# 02-PowerSupply.net
KiCad netlist of a schematic drawn in Altium Designer
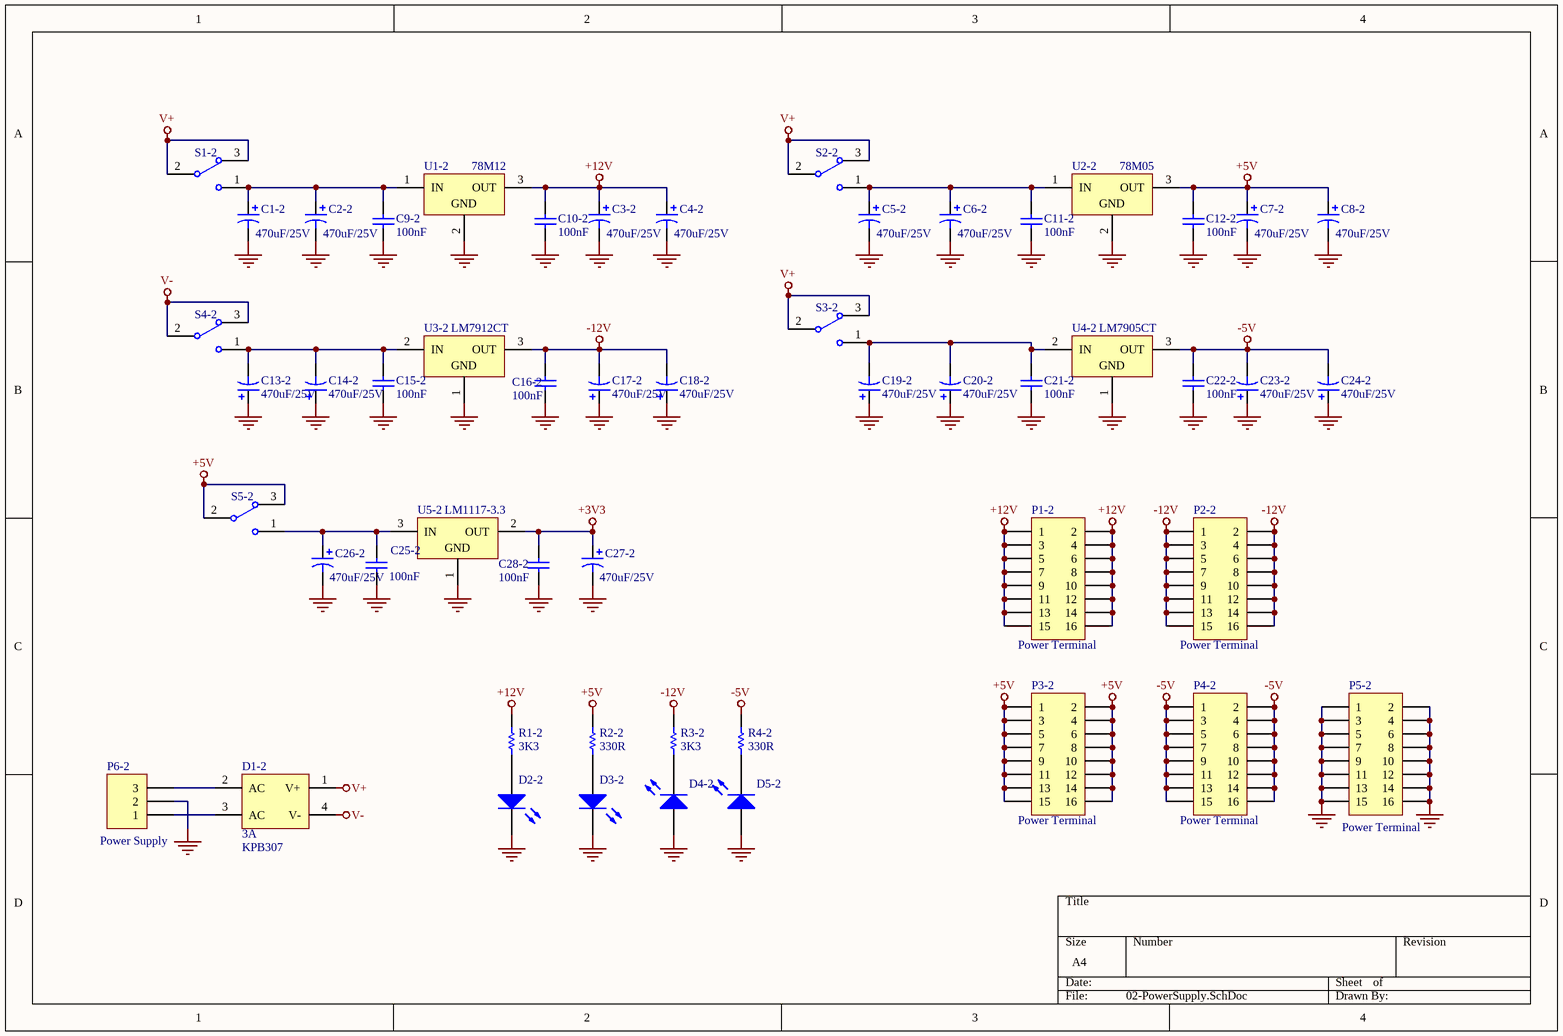
[diagram p0: 02-PowerSupply.SchDoc]

(export (version "E")
  (design (tool "Eeschema 10.0.6"))
  (components
    (comp (ref "C1-2")
      (value "470uF/25V")
      (footprint "C-ALU-10x10mm")
      (description "Polarized Capacitor (Radial)")
      (libsource (lib "Miscellaneous Devices") (part "Cap Pol1"))
    )
    (comp (ref "C2-2")
      (value "470uF/25V")
      (footprint "C-ALU-10x10mm")
      (description "Polarized Capacitor (Radial)")
      (libsource (lib "Miscellaneous Devices") (part "Cap Pol1"))
    )
    (comp (ref "C3-2")
      (value "470uF/25V")
      (footprint "C-ALU-10x10mm")
      (description "Polarized Capacitor (Radial)")
      (libsource (lib "Miscellaneous Devices") (part "Cap Pol1"))
    )
    (comp (ref "C4-2")
      (value "470uF/25V")
      (footprint "C-ALU-10x10mm")
      (description "Polarized Capacitor (Radial)")
      (libsource (lib "Miscellaneous Devices") (part "Cap Pol1"))
    )
    (comp (ref "C5-2")
      (value "470uF/25V")
      (footprint "C-ALU-10x10mm")
      (description "Polarized Capacitor (Radial)")
      (libsource (lib "Miscellaneous Devices") (part "Cap Pol1"))
    )
    (comp (ref "C6-2")
      (value "470uF/25V")
      (footprint "C-ALU-10x10mm")
      (description "Polarized Capacitor (Radial)")
      (libsource (lib "Miscellaneous Devices") (part "Cap Pol1"))
    )
    (comp (ref "C7-2")
      (value "470uF/25V")
      (footprint "C-ALU-10x10mm")
      (description "Polarized Capacitor (Radial)")
      (libsource (lib "Miscellaneous Devices") (part "Cap Pol1"))
    )
    (comp (ref "C8-2")
      (value "470uF/25V")
      (footprint "C-ALU-10x10mm")
      (description "Polarized Capacitor (Radial)")
      (libsource (lib "Miscellaneous Devices") (part "Cap Pol1"))
    )
    (comp (ref "C9-2")
      (value "100nF")
      (footprint "c-0805")
      (description "Capacitor")
      (fields
        (field (name "MANUFACTURER") "Generic Components")
        (field (name "Comment") "104")
        (field (name "PUBLISHER") "Altium Hobart Technology Centre")
      )
      (libsource (lib "Miscellaneous Devices") (part "Cap"))
    )
    (comp (ref "C10-2")
      (value "100nF")
      (footprint "c-0805")
      (description "Capacitor")
      (fields
        (field (name "MANUFACTURER") "Generic Components")
        (field (name "Comment") "104")
        (field (name "PUBLISHER") "Altium Hobart Technology Centre")
      )
      (libsource (lib "Miscellaneous Devices") (part "Cap"))
    )
    (comp (ref "C11-2")
      (value "100nF")
      (footprint "c-0805")
      (description "Capacitor")
      (fields
        (field (name "MANUFACTURER") "Generic Components")
        (field (name "Comment") "104")
        (field (name "PUBLISHER") "Altium Hobart Technology Centre")
      )
      (libsource (lib "Miscellaneous Devices") (part "Cap"))
    )
    (comp (ref "C12-2")
      (value "100nF")
      (footprint "c-0805")
      (description "Capacitor")
      (fields
        (field (name "MANUFACTURER") "Generic Components")
        (field (name "Comment") "104")
        (field (name "PUBLISHER") "Altium Hobart Technology Centre")
      )
      (libsource (lib "Miscellaneous Devices") (part "Cap"))
    )
    (comp (ref "C13-2")
      (value "470uF/25V")
      (footprint "C-ALU-10x10mm")
      (description "Polarized Capacitor (Radial)")
      (libsource (lib "Miscellaneous Devices") (part "Cap Pol1"))
    )
    (comp (ref "C14-2")
      (value "470uF/25V")
      (footprint "C-ALU-10x10mm")
      (description "Polarized Capacitor (Radial)")
      (libsource (lib "Miscellaneous Devices") (part "Cap Pol1"))
    )
    (comp (ref "C15-2")
      (value "100nF")
      (footprint "c-0805")
      (description "Capacitor")
      (fields
        (field (name "MANUFACTURER") "Generic Components")
        (field (name "Comment") "104")
        (field (name "PUBLISHER") "Altium Hobart Technology Centre")
      )
      (libsource (lib "Miscellaneous Devices") (part "Cap"))
    )
    (comp (ref "C16-2")
      (value "100nF")
      (footprint "c-0805")
      (description "Capacitor")
      (fields
        (field (name "MANUFACTURER") "Generic Components")
        (field (name "Comment") "104")
        (field (name "PUBLISHER") "Altium Hobart Technology Centre")
      )
      (libsource (lib "Miscellaneous Devices") (part "Cap"))
    )
    (comp (ref "C17-2")
      (value "470uF/25V")
      (footprint "C-ALU-10x10mm")
      (description "Polarized Capacitor (Radial)")
      (libsource (lib "Miscellaneous Devices") (part "Cap Pol1"))
    )
    (comp (ref "C18-2")
      (value "470uF/25V")
      (footprint "C-ALU-10x10mm")
      (description "Polarized Capacitor (Radial)")
      (libsource (lib "Miscellaneous Devices") (part "Cap Pol1"))
    )
    (comp (ref "C19-2")
      (value "470uF/25V")
      (footprint "C-ALU-10x10mm")
      (description "Polarized Capacitor (Radial)")
      (libsource (lib "Miscellaneous Devices") (part "Cap Pol1"))
    )
    (comp (ref "C20-2")
      (value "470uF/25V")
      (footprint "C-ALU-10x10mm")
      (description "Polarized Capacitor (Radial)")
      (libsource (lib "Miscellaneous Devices") (part "Cap Pol1"))
    )
    (comp (ref "C21-2")
      (value "100nF")
      (footprint "c-0805")
      (description "Capacitor")
      (fields
        (field (name "MANUFACTURER") "Generic Components")
        (field (name "Comment") "104")
        (field (name "PUBLISHER") "Altium Hobart Technology Centre")
      )
      (libsource (lib "Miscellaneous Devices") (part "Cap"))
    )
    (comp (ref "C22-2")
      (value "100nF")
      (footprint "c-0805")
      (description "Capacitor")
      (fields
        (field (name "MANUFACTURER") "Generic Components")
        (field (name "Comment") "104")
        (field (name "PUBLISHER") "Altium Hobart Technology Centre")
      )
      (libsource (lib "Miscellaneous Devices") (part "Cap"))
    )
    (comp (ref "C23-2")
      (value "470uF/25V")
      (footprint "C-ALU-10x10mm")
      (description "Polarized Capacitor (Radial)")
      (libsource (lib "Miscellaneous Devices") (part "Cap Pol1"))
    )
    (comp (ref "C24-2")
      (value "470uF/25V")
      (footprint "C-ALU-10x10mm")
      (description "Polarized Capacitor (Radial)")
      (libsource (lib "Miscellaneous Devices") (part "Cap Pol1"))
    )
    (comp (ref "C25-2")
      (value "100nF")
      (footprint "c-0805")
      (description "Capacitor")
      (fields
        (field (name "MANUFACTURER") "Generic Components")
        (field (name "Comment") "104")
        (field (name "PUBLISHER") "Altium Hobart Technology Centre")
      )
      (libsource (lib "Miscellaneous Devices") (part "Cap"))
    )
    (comp (ref "C26-2")
      (value "470uF/25V")
      (footprint "C-ALU-10x10mm")
      (description "Polarized Capacitor (Radial)")
      (libsource (lib "Miscellaneous Devices") (part "Cap Pol1"))
    )
    (comp (ref "C27-2")
      (value "470uF/25V")
      (footprint "C-ALU-10x10mm")
      (description "Polarized Capacitor (Radial)")
      (libsource (lib "Miscellaneous Devices") (part "Cap Pol1"))
    )
    (comp (ref "C28-2")
      (value "100nF")
      (footprint "c-0805")
      (description "Capacitor")
      (fields
        (field (name "MANUFACTURER") "Generic Components")
        (field (name "Comment") "104")
        (field (name "PUBLISHER") "Altium Hobart Technology Centre")
      )
      (libsource (lib "Miscellaneous Devices") (part "Cap"))
    )
    (comp (ref "D1-2")
      (value "KPB307")
      (footprint "D-DB-3A")
      (description "Diode Bridge")
      (fields (field (name "ALTIUM_VALUE") "3A"))
      (libsource (lib "Miscellaneous Devices") (part "Bridge2"))
    )
    (comp (ref "D2-2")
      (value "LED")
      (footprint "LED-0805")
      (description "Typical INFRARED GaAs LED")
      (fields (field (name "PUBLISHER") "Altium Limited"))
      (libsource (lib "Miscellaneous Devices") (part "LED0"))
    )
    (comp (ref "D3-2")
      (value "LED")
      (footprint "LED-0805")
      (description "Typical INFRARED GaAs LED")
      (fields (field (name "PUBLISHER") "Altium Limited"))
      (libsource (lib "Miscellaneous Devices") (part "LED0"))
    )
    (comp (ref "D4-2")
      (value "LED")
      (footprint "LED-0805")
      (description "Typical INFRARED GaAs LED")
      (fields (field (name "PUBLISHER") "Altium Limited"))
      (libsource (lib "Miscellaneous Devices") (part "LED0"))
    )
    (comp (ref "D5-2")
      (value "LED")
      (footprint "LED-0805")
      (description "Typical INFRARED GaAs LED")
      (fields (field (name "PUBLISHER") "Altium Limited"))
      (libsource (lib "Miscellaneous Devices") (part "LED0"))
    )
    (comp (ref "P1-2")
      (value "Power Terminal")
      (footprint "JP2.54-F-2x08A")
      (description "Header, 8-Pin, Dual row")
      (fields (field (name "Comment") "Header 8X2"))
      (libsource (lib "Miscellaneous Connectors") (part "Header 8X2"))
    )
    (comp (ref "P2-2")
      (value "Power Terminal")
      (footprint "JP2.54-F-2x08A")
      (description "Header, 8-Pin, Dual row")
      (fields (field (name "Comment") "Header 8X2"))
      (libsource (lib "Miscellaneous Connectors") (part "Header 8X2"))
    )
    (comp (ref "P3-2")
      (value "Power Terminal")
      (footprint "JP2.54-F-2x08A")
      (description "Header, 8-Pin, Dual row")
      (fields (field (name "Comment") "Header 8X2"))
      (libsource (lib "Miscellaneous Connectors") (part "Header 8X2"))
    )
    (comp (ref "P4-2")
      (value "Power Terminal")
      (footprint "JP2.54-F-2x08A")
      (description "Header, 8-Pin, Dual row")
      (fields (field (name "Comment") "Header 8X2"))
      (libsource (lib "Miscellaneous Connectors") (part "Header 8X2"))
    )
    (comp (ref "P5-2")
      (value "Power Terminal")
      (footprint "JP2.54-F-2x08A")
      (description "Header, 8-Pin, Dual row")
      (fields (field (name "Comment") "Header 8X2"))
      (libsource (lib "Miscellaneous Connectors") (part "Header 8X2"))
    )
    (comp (ref "P6-2")
      (value "Power Supply")
      (footprint "TER-KF128-3")
      (description "Header, 3-Pin")
      (fields (field (name "Comment") "H3"))
      (libsource (lib "Miscellaneous Connectors") (part "Header 3"))
    )
    (comp (ref "R1-2")
      (value "3K3")
      (footprint "R-0805")
      (description "Resistor")
      (fields (field (name "Comment") "332") (field (name "PUBLISHER") "Altium Limited"))
      (libsource (lib "Miscellaneous Devices") (part "Res1"))
    )
    (comp (ref "R2-2")
      (value "330R")
      (footprint "R-0805")
      (description "Resistor")
      (fields (field (name "Comment") "331") (field (name "PUBLISHER") "Altium Limited"))
      (libsource (lib "Miscellaneous Devices") (part "Res1"))
    )
    (comp (ref "R3-2")
      (value "3K3")
      (footprint "R-0805")
      (description "Resistor")
      (fields (field (name "Comment") "332") (field (name "PUBLISHER") "Altium Limited"))
      (libsource (lib "Miscellaneous Devices") (part "Res1"))
    )
    (comp (ref "R4-2")
      (value "330R")
      (footprint "R-0805")
      (description "Resistor")
      (fields (field (name "Comment") "331") (field (name "PUBLISHER") "Altium Limited"))
      (libsource (lib "Miscellaneous Devices") (part "Res1"))
    )
    (comp (ref "S1-2")
      (value "SW-SPDT")
      (footprint "SW-SLIDE-2P-2W")
      (description "SPDT Subminiature Toggle Switch, Right Angle Mounting, Vertical Actuation")
      (libsource (lib "Miscellaneous Devices") (part "SW-SPDT"))
    )
    (comp (ref "S2-2")
      (value "SW-SPDT")
      (footprint "SW-SLIDE-2P-2W")
      (description "SPDT Subminiature Toggle Switch, Right Angle Mounting, Vertical Actuation")
      (libsource (lib "Miscellaneous Devices") (part "SW-SPDT"))
    )
    (comp (ref "S3-2")
      (value "SW-SPDT")
      (footprint "SW-SLIDE-2P-2W")
      (description "SPDT Subminiature Toggle Switch, Right Angle Mounting, Vertical Actuation")
      (libsource (lib "Miscellaneous Devices") (part "SW-SPDT"))
    )
    (comp (ref "S4-2")
      (value "SW-SPDT")
      (footprint "SW-SLIDE-2P-2W")
      (description "SPDT Subminiature Toggle Switch, Right Angle Mounting, Vertical Actuation")
      (libsource (lib "Miscellaneous Devices") (part "SW-SPDT"))
    )
    (comp (ref "S5-2")
      (value "SW-SPDT")
      (footprint "SW-SLIDE-2P-2W")
      (description "SPDT Subminiature Toggle Switch, Right Angle Mounting, Vertical Actuation")
      (libsource (lib "Miscellaneous Devices") (part "SW-SPDT"))
    )
    (comp (ref "U1-2")
      (value "78M12")
      (footprint "TO-252-3")
      (description "3-Terminal Positive Voltage Regulators, 3-pin TO-220")
      (fields
        (field (name "PARTNUMBER") "LM78M05CT")
        (field (name "MANUFACTURER") "National Semiconductor")
        (field (name "PUBLISHER") "Altium Limited")
      )
      (libsource (lib "NSC LDO") (part "LM78M05CT"))
    )
    (comp (ref "U2-2")
      (value "78M05")
      (footprint "TO-252-3")
      (description "3-Terminal Positive Voltage Regulators, 3-pin TO-220")
      (fields
        (field (name "PARTNUMBER") "LM78M05CT")
        (field (name "MANUFACTURER") "National Semiconductor")
        (field (name "PUBLISHER") "Altium Limited")
      )
      (libsource (lib "NSC LDO") (part "LM78M05CT"))
    )
    (comp (ref "U3-2")
      (value "LM7912CT")
      (footprint "TO-263-3")
      (description "3-Terminal Negative Regulators, 3-pin TO-220")
      (fields
        (field (name "PARTNUMBER") "LM79M12CT")
        (field (name "MANUFACTURER") "National Semiconductor")
        (field (name "PUBLISHER") "Altium Limited")
      )
      (libsource (lib "NSC LDO") (part "LM79M12CT"))
    )
    (comp (ref "U4-2")
      (value "LM7905CT")
      (footprint "TO-263-3")
      (description "3-Terminal Negative Regulators, 3-pin TO-220")
      (fields
        (field (name "PARTNUMBER") "LM79M12CT")
        (field (name "MANUFACTURER") "National Semiconductor")
        (field (name "PUBLISHER") "Altium Limited")
      )
      (libsource (lib "NSC LDO") (part "LM79M12CT"))
    )
    (comp (ref "U5-2")
      (value "LM1117-3.3")
      (footprint "SOT-223-3")
      (description "800mA Low-Dropout Linear Regulator, 3-pin TO-252")
      (fields
        (field (name "PARTNUMBER") "LM1117IDTX-3.3")
        (field (name "MANUFACTURER") "National Semiconductor")
        (field (name "PUBLISHER") "Altium Limited")
      )
      (libsource (lib "NSC LDO") (part "LM1117IDTX-3.3"))
    )
  )
  (nets
    (net (code "1") (name "+3V3") (class "Default")
      (node (ref "C27-2") (pin "1") (pinfunction "1_1") (pintype "passive"))
      (node (ref "C28-2") (pin "2") (pinfunction "2_2") (pintype "passive"))
      (node (ref "U5-2") (pin "2") (pinfunction "OUT_2") (pintype "power_in"))
    )
    (net (code "2") (name "+5V") (class "Default")
      (node (ref "C12-2") (pin "2") (pinfunction "2_2") (pintype "passive"))
      (node (ref "C7-2") (pin "1") (pinfunction "1_1") (pintype "passive"))
      (node (ref "C8-2") (pin "1") (pinfunction "1_1") (pintype "passive"))
      (node (ref "P3-2") (pin "1") (pinfunction "1_1") (pintype "passive"))
      (node (ref "P3-2") (pin "10") (pinfunction "10_10") (pintype "passive"))
      (node (ref "P3-2") (pin "11") (pinfunction "11_11") (pintype "passive"))
      (node (ref "P3-2") (pin "12") (pinfunction "12_12") (pintype "passive"))
      (node (ref "P3-2") (pin "13") (pinfunction "13_13") (pintype "passive"))
      (node (ref "P3-2") (pin "14") (pinfunction "14_14") (pintype "passive"))
      (node (ref "P3-2") (pin "15") (pinfunction "15_15") (pintype "passive"))
      (node (ref "P3-2") (pin "16") (pinfunction "16_16") (pintype "passive"))
      (node (ref "P3-2") (pin "2") (pinfunction "2_2") (pintype "passive"))
      (node (ref "P3-2") (pin "3") (pinfunction "3_3") (pintype "passive"))
      (node (ref "P3-2") (pin "4") (pinfunction "4_4") (pintype "passive"))
      (node (ref "P3-2") (pin "5") (pinfunction "5_5") (pintype "passive"))
      (node (ref "P3-2") (pin "6") (pinfunction "6_6") (pintype "passive"))
      (node (ref "P3-2") (pin "7") (pinfunction "7_7") (pintype "passive"))
      (node (ref "P3-2") (pin "8") (pinfunction "8_8") (pintype "passive"))
      (node (ref "P3-2") (pin "9") (pinfunction "9_9") (pintype "passive"))
      (node (ref "R2-2") (pin "1") (pinfunction "1_1") (pintype "passive"))
      (node (ref "S5-2") (pin "2") (pinfunction "2_2") (pintype "passive"))
      (node (ref "S5-2") (pin "3") (pinfunction "3_3") (pintype "passive"))
      (node (ref "U2-2") (pin "3") (pinfunction "OUT_3") (pintype "power_in"))
    )
    (net (code "3") (name "+12V") (class "Default")
      (node (ref "C10-2") (pin "2") (pinfunction "2_2") (pintype "passive"))
      (node (ref "C3-2") (pin "1") (pinfunction "1_1") (pintype "passive"))
      (node (ref "C4-2") (pin "1") (pinfunction "1_1") (pintype "passive"))
      (node (ref "P1-2") (pin "1") (pinfunction "1_1") (pintype "passive"))
      (node (ref "P1-2") (pin "10") (pinfunction "10_10") (pintype "passive"))
      (node (ref "P1-2") (pin "11") (pinfunction "11_11") (pintype "passive"))
      (node (ref "P1-2") (pin "12") (pinfunction "12_12") (pintype "passive"))
      (node (ref "P1-2") (pin "13") (pinfunction "13_13") (pintype "passive"))
      (node (ref "P1-2") (pin "14") (pinfunction "14_14") (pintype "passive"))
      (node (ref "P1-2") (pin "15") (pinfunction "15_15") (pintype "passive"))
      (node (ref "P1-2") (pin "16") (pinfunction "16_16") (pintype "passive"))
      (node (ref "P1-2") (pin "2") (pinfunction "2_2") (pintype "passive"))
      (node (ref "P1-2") (pin "3") (pinfunction "3_3") (pintype "passive"))
      (node (ref "P1-2") (pin "4") (pinfunction "4_4") (pintype "passive"))
      (node (ref "P1-2") (pin "5") (pinfunction "5_5") (pintype "passive"))
      (node (ref "P1-2") (pin "6") (pinfunction "6_6") (pintype "passive"))
      (node (ref "P1-2") (pin "7") (pinfunction "7_7") (pintype "passive"))
      (node (ref "P1-2") (pin "8") (pinfunction "8_8") (pintype "passive"))
      (node (ref "P1-2") (pin "9") (pinfunction "9_9") (pintype "passive"))
      (node (ref "R1-2") (pin "1") (pinfunction "1_1") (pintype "passive"))
      (node (ref "U1-2") (pin "3") (pinfunction "OUT_3") (pintype "power_in"))
    )
    (net (code "4") (name "-5V") (class "Default")
      (node (ref "C22-2") (pin "2") (pinfunction "2_2") (pintype "passive"))
      (node (ref "C23-2") (pin "2") (pinfunction "2_2") (pintype "passive"))
      (node (ref "C24-2") (pin "2") (pinfunction "2_2") (pintype "passive"))
      (node (ref "P4-2") (pin "1") (pinfunction "1_1") (pintype "passive"))
      (node (ref "P4-2") (pin "10") (pinfunction "10_10") (pintype "passive"))
      (node (ref "P4-2") (pin "11") (pinfunction "11_11") (pintype "passive"))
      (node (ref "P4-2") (pin "12") (pinfunction "12_12") (pintype "passive"))
      (node (ref "P4-2") (pin "13") (pinfunction "13_13") (pintype "passive"))
      (node (ref "P4-2") (pin "14") (pinfunction "14_14") (pintype "passive"))
      (node (ref "P4-2") (pin "15") (pinfunction "15_15") (pintype "passive"))
      (node (ref "P4-2") (pin "16") (pinfunction "16_16") (pintype "passive"))
      (node (ref "P4-2") (pin "2") (pinfunction "2_2") (pintype "passive"))
      (node (ref "P4-2") (pin "3") (pinfunction "3_3") (pintype "passive"))
      (node (ref "P4-2") (pin "4") (pinfunction "4_4") (pintype "passive"))
      (node (ref "P4-2") (pin "5") (pinfunction "5_5") (pintype "passive"))
      (node (ref "P4-2") (pin "6") (pinfunction "6_6") (pintype "passive"))
      (node (ref "P4-2") (pin "7") (pinfunction "7_7") (pintype "passive"))
      (node (ref "P4-2") (pin "8") (pinfunction "8_8") (pintype "passive"))
      (node (ref "P4-2") (pin "9") (pinfunction "9_9") (pintype "passive"))
      (node (ref "R4-2") (pin "1") (pinfunction "1_1") (pintype "passive"))
      (node (ref "U4-2") (pin "3") (pinfunction "OUT_3") (pintype "power_in"))
    )
    (net (code "5") (name "-12V") (class "Default")
      (node (ref "C16-2") (pin "2") (pinfunction "2_2") (pintype "passive"))
      (node (ref "C17-2") (pin "2") (pinfunction "2_2") (pintype "passive"))
      (node (ref "C18-2") (pin "2") (pinfunction "2_2") (pintype "passive"))
      (node (ref "P2-2") (pin "1") (pinfunction "1_1") (pintype "passive"))
      (node (ref "P2-2") (pin "10") (pinfunction "10_10") (pintype "passive"))
      (node (ref "P2-2") (pin "11") (pinfunction "11_11") (pintype "passive"))
      (node (ref "P2-2") (pin "12") (pinfunction "12_12") (pintype "passive"))
      (node (ref "P2-2") (pin "13") (pinfunction "13_13") (pintype "passive"))
      (node (ref "P2-2") (pin "14") (pinfunction "14_14") (pintype "passive"))
      (node (ref "P2-2") (pin "15") (pinfunction "15_15") (pintype "passive"))
      (node (ref "P2-2") (pin "16") (pinfunction "16_16") (pintype "passive"))
      (node (ref "P2-2") (pin "2") (pinfunction "2_2") (pintype "passive"))
      (node (ref "P2-2") (pin "3") (pinfunction "3_3") (pintype "passive"))
      (node (ref "P2-2") (pin "4") (pinfunction "4_4") (pintype "passive"))
      (node (ref "P2-2") (pin "5") (pinfunction "5_5") (pintype "passive"))
      (node (ref "P2-2") (pin "6") (pinfunction "6_6") (pintype "passive"))
      (node (ref "P2-2") (pin "7") (pinfunction "7_7") (pintype "passive"))
      (node (ref "P2-2") (pin "8") (pinfunction "8_8") (pintype "passive"))
      (node (ref "P2-2") (pin "9") (pinfunction "9_9") (pintype "passive"))
      (node (ref "R3-2") (pin "1") (pinfunction "1_1") (pintype "passive"))
      (node (ref "U3-2") (pin "3") (pinfunction "OUT_3") (pintype "power_in"))
    )
    (net (code "6") (name "GND") (class "Default")
      (node (ref "C1-2") (pin "2") (pinfunction "2_2") (pintype "passive"))
      (node (ref "C10-2") (pin "1") (pinfunction "1_1") (pintype "passive"))
      (node (ref "C11-2") (pin "1") (pinfunction "1_1") (pintype "passive"))
      (node (ref "C12-2") (pin "1") (pinfunction "1_1") (pintype "passive"))
      (node (ref "C13-2") (pin "1") (pinfunction "1_1") (pintype "passive"))
      (node (ref "C14-2") (pin "1") (pinfunction "1_1") (pintype "passive"))
      (node (ref "C15-2") (pin "1") (pinfunction "1_1") (pintype "passive"))
      (node (ref "C16-2") (pin "1") (pinfunction "1_1") (pintype "passive"))
      (node (ref "C17-2") (pin "1") (pinfunction "1_1") (pintype "passive"))
      (node (ref "C18-2") (pin "1") (pinfunction "1_1") (pintype "passive"))
      (node (ref "C19-2") (pin "1") (pinfunction "1_1") (pintype "passive"))
      (node (ref "C2-2") (pin "2") (pinfunction "2_2") (pintype "passive"))
      (node (ref "C20-2") (pin "1") (pinfunction "1_1") (pintype "passive"))
      (node (ref "C21-2") (pin "1") (pinfunction "1_1") (pintype "passive"))
      (node (ref "C22-2") (pin "1") (pinfunction "1_1") (pintype "passive"))
      (node (ref "C23-2") (pin "1") (pinfunction "1_1") (pintype "passive"))
      (node (ref "C24-2") (pin "1") (pinfunction "1_1") (pintype "passive"))
      (node (ref "C25-2") (pin "1") (pinfunction "1_1") (pintype "passive"))
      (node (ref "C26-2") (pin "2") (pinfunction "2_2") (pintype "passive"))
      (node (ref "C27-2") (pin "2") (pinfunction "2_2") (pintype "passive"))
      (node (ref "C28-2") (pin "1") (pinfunction "1_1") (pintype "passive"))
      (node (ref "C3-2") (pin "2") (pinfunction "2_2") (pintype "passive"))
      (node (ref "C4-2") (pin "2") (pinfunction "2_2") (pintype "passive"))
      (node (ref "C5-2") (pin "2") (pinfunction "2_2") (pintype "passive"))
      (node (ref "C6-2") (pin "2") (pinfunction "2_2") (pintype "passive"))
      (node (ref "C7-2") (pin "2") (pinfunction "2_2") (pintype "passive"))
      (node (ref "C8-2") (pin "2") (pinfunction "2_2") (pintype "passive"))
      (node (ref "C9-2") (pin "1") (pinfunction "1_1") (pintype "passive"))
      (node (ref "D2-2") (pin "1") (pinfunction "K_1") (pintype "passive"))
      (node (ref "D3-2") (pin "1") (pinfunction "K_1") (pintype "passive"))
      (node (ref "D4-2") (pin "2") (pinfunction "A_2") (pintype "passive"))
      (node (ref "D5-2") (pin "2") (pinfunction "A_2") (pintype "passive"))
      (node (ref "P5-2") (pin "1") (pinfunction "1_1") (pintype "passive"))
      (node (ref "P5-2") (pin "10") (pinfunction "10_10") (pintype "passive"))
      (node (ref "P5-2") (pin "11") (pinfunction "11_11") (pintype "passive"))
      (node (ref "P5-2") (pin "12") (pinfunction "12_12") (pintype "passive"))
      (node (ref "P5-2") (pin "13") (pinfunction "13_13") (pintype "passive"))
      (node (ref "P5-2") (pin "14") (pinfunction "14_14") (pintype "passive"))
      (node (ref "P5-2") (pin "15") (pinfunction "15_15") (pintype "passive"))
      (node (ref "P5-2") (pin "16") (pinfunction "16_16") (pintype "passive"))
      (node (ref "P5-2") (pin "2") (pinfunction "2_2") (pintype "passive"))
      (node (ref "P5-2") (pin "3") (pinfunction "3_3") (pintype "passive"))
      (node (ref "P5-2") (pin "4") (pinfunction "4_4") (pintype "passive"))
      (node (ref "P5-2") (pin "5") (pinfunction "5_5") (pintype "passive"))
      (node (ref "P5-2") (pin "6") (pinfunction "6_6") (pintype "passive"))
      (node (ref "P5-2") (pin "7") (pinfunction "7_7") (pintype "passive"))
      (node (ref "P5-2") (pin "8") (pinfunction "8_8") (pintype "passive"))
      (node (ref "P5-2") (pin "9") (pinfunction "9_9") (pintype "passive"))
      (node (ref "P6-2") (pin "2") (pinfunction "2_2") (pintype "passive"))
      (node (ref "U1-2") (pin "2") (pinfunction "GND_2") (pintype "power_in"))
      (node (ref "U2-2") (pin "2") (pinfunction "GND_2") (pintype "power_in"))
      (node (ref "U3-2") (pin "1") (pinfunction "GND_1") (pintype "power_in"))
      (node (ref "U4-2") (pin "1") (pinfunction "GND_1") (pintype "power_in"))
      (node (ref "U5-2") (pin "1") (pinfunction "GND_1") (pintype "power_in"))
    )
    (net (code "7") (name "Net-(D1-2-AC-Pad2)") (class "Default")
      (node (ref "D1-2") (pin "2") (pinfunction "AC_2") (pintype "passive"))
      (node (ref "P6-2") (pin "3") (pinfunction "3_3") (pintype "passive"))
    )
    (net (code "8") (name "Net-(D1-2-AC-Pad3)") (class "Default")
      (node (ref "D1-2") (pin "3") (pinfunction "AC_3") (pintype "passive"))
      (node (ref "P6-2") (pin "1") (pinfunction "1_1") (pintype "passive"))
    )
    (net (code "9") (name "Net-(D2-2-A)") (class "Default")
      (node (ref "D2-2") (pin "2") (pinfunction "A_2") (pintype "passive"))
      (node (ref "R1-2") (pin "2") (pinfunction "2_2") (pintype "passive"))
    )
    (net (code "10") (name "Net-(D3-2-A)") (class "Default")
      (node (ref "D3-2") (pin "2") (pinfunction "A_2") (pintype "passive"))
      (node (ref "R2-2") (pin "2") (pinfunction "2_2") (pintype "passive"))
    )
    (net (code "11") (name "Net-(D4-2-K)") (class "Default")
      (node (ref "D4-2") (pin "1") (pinfunction "K_1") (pintype "passive"))
      (node (ref "R3-2") (pin "2") (pinfunction "2_2") (pintype "passive"))
    )
    (net (code "12") (name "Net-(D5-2-K)") (class "Default")
      (node (ref "D5-2") (pin "1") (pinfunction "K_1") (pintype "passive"))
      (node (ref "R4-2") (pin "2") (pinfunction "2_2") (pintype "passive"))
    )
    (net (code "13") (name "Net-(U1-2-IN)") (class "Default")
      (node (ref "C1-2") (pin "1") (pinfunction "1_1") (pintype "passive"))
      (node (ref "C2-2") (pin "1") (pinfunction "1_1") (pintype "passive"))
      (node (ref "C9-2") (pin "2") (pinfunction "2_2") (pintype "passive"))
      (node (ref "S1-2") (pin "1") (pinfunction "1_1") (pintype "passive"))
      (node (ref "U1-2") (pin "1") (pinfunction "IN_1") (pintype "power_in"))
    )
    (net (code "14") (name "Net-(U2-2-IN)") (class "Default")
      (node (ref "C11-2") (pin "2") (pinfunction "2_2") (pintype "passive"))
      (node (ref "C5-2") (pin "1") (pinfunction "1_1") (pintype "passive"))
      (node (ref "C6-2") (pin "1") (pinfunction "1_1") (pintype "passive"))
      (node (ref "S2-2") (pin "1") (pinfunction "1_1") (pintype "passive"))
      (node (ref "U2-2") (pin "1") (pinfunction "IN_1") (pintype "power_in"))
    )
    (net (code "15") (name "Net-(U3-2-IN)") (class "Default")
      (node (ref "C13-2") (pin "2") (pinfunction "2_2") (pintype "passive"))
      (node (ref "C14-2") (pin "2") (pinfunction "2_2") (pintype "passive"))
      (node (ref "C15-2") (pin "2") (pinfunction "2_2") (pintype "passive"))
      (node (ref "S4-2") (pin "1") (pinfunction "1_1") (pintype "passive"))
      (node (ref "U3-2") (pin "2") (pinfunction "IN_2") (pintype "power_in"))
    )
    (net (code "16") (name "Net-(U4-2-IN)") (class "Default")
      (node (ref "C19-2") (pin "2") (pinfunction "2_2") (pintype "passive"))
      (node (ref "C20-2") (pin "2") (pinfunction "2_2") (pintype "passive"))
      (node (ref "C21-2") (pin "2") (pinfunction "2_2") (pintype "passive"))
      (node (ref "S3-2") (pin "1") (pinfunction "1_1") (pintype "passive"))
      (node (ref "U4-2") (pin "2") (pinfunction "IN_2") (pintype "power_in"))
    )
    (net (code "17") (name "Net-(U5-2-IN)") (class "Default")
      (node (ref "C25-2") (pin "2") (pinfunction "2_2") (pintype "passive"))
      (node (ref "C26-2") (pin "1") (pinfunction "1_1") (pintype "passive"))
      (node (ref "S5-2") (pin "1") (pinfunction "1_1") (pintype "passive"))
      (node (ref "U5-2") (pin "3") (pinfunction "IN_3") (pintype "power_in"))
    )
    (net (code "18") (name "V+") (class "Default")
      (node (ref "D1-2") (pin "1") (pinfunction "V+_1") (pintype "passive"))
      (node (ref "S1-2") (pin "2") (pinfunction "2_2") (pintype "passive"))
      (node (ref "S1-2") (pin "3") (pinfunction "3_3") (pintype "passive"))
      (node (ref "S2-2") (pin "2") (pinfunction "2_2") (pintype "passive"))
      (node (ref "S2-2") (pin "3") (pinfunction "3_3") (pintype "passive"))
      (node (ref "S3-2") (pin "2") (pinfunction "2_2") (pintype "passive"))
      (node (ref "S3-2") (pin "3") (pinfunction "3_3") (pintype "passive"))
    )
    (net (code "19") (name "V-") (class "Default")
      (node (ref "D1-2") (pin "4") (pinfunction "V-_4") (pintype "passive"))
      (node (ref "S4-2") (pin "2") (pinfunction "2_2") (pintype "passive"))
      (node (ref "S4-2") (pin "3") (pinfunction "3_3") (pintype "passive"))
    )
  )
)
